# FerroAudioAmp.net
KiCad netlist of a schematic drawn in Altium Designer
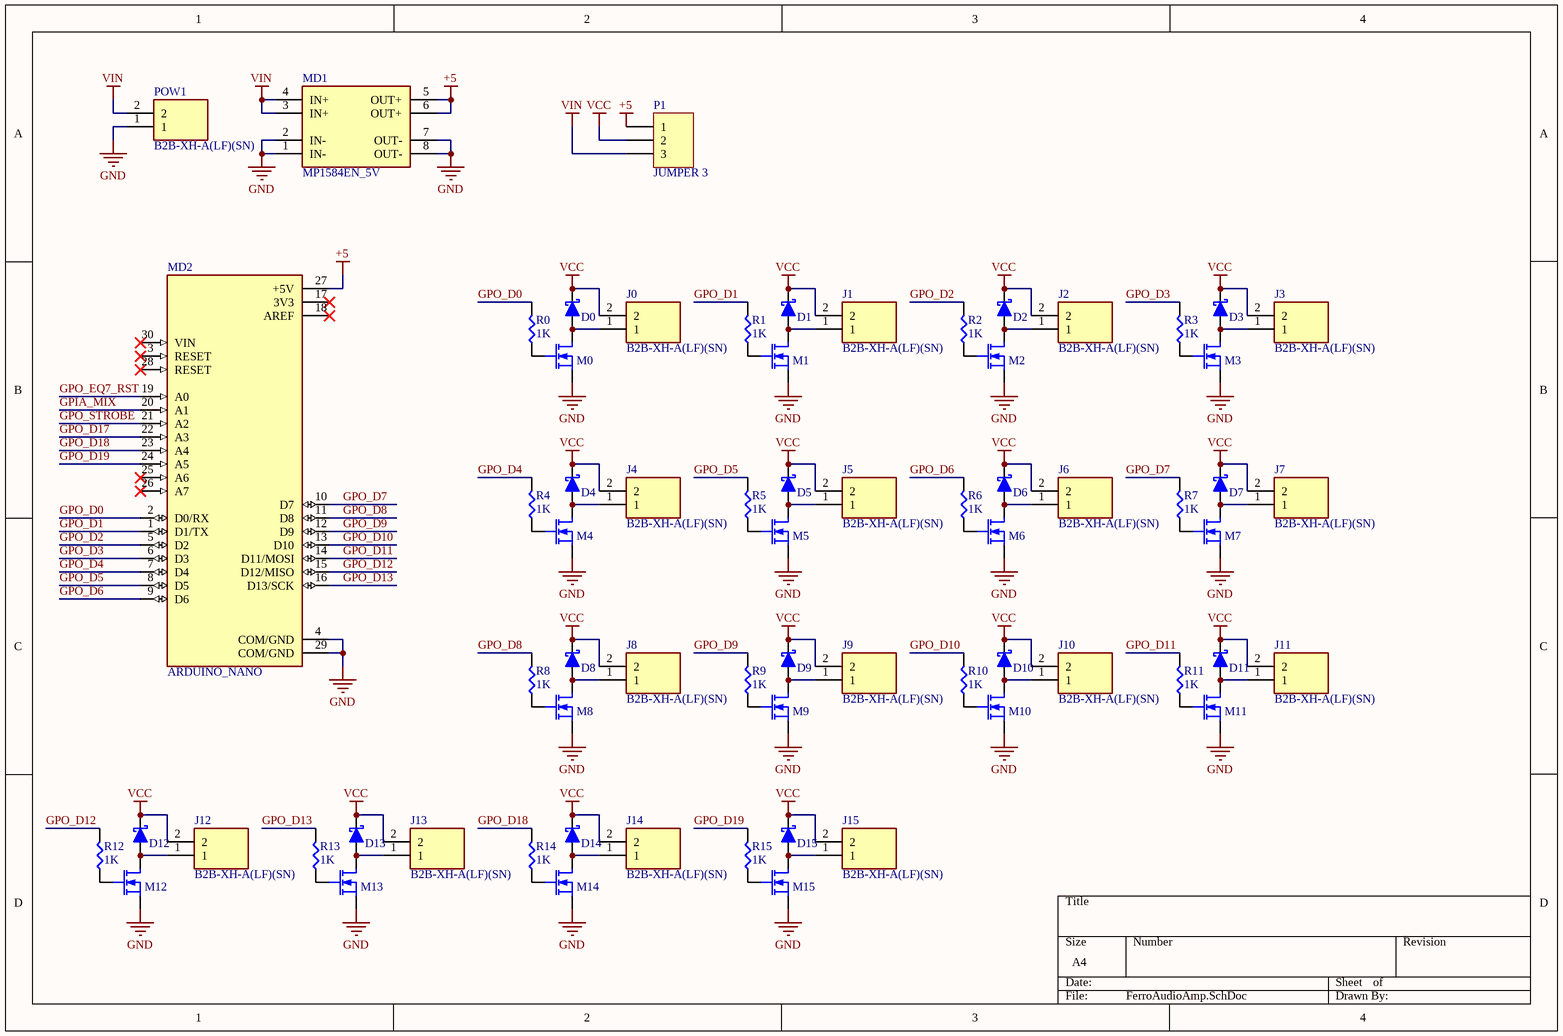
[diagram p0: FerroAudioAmp.SchDoc]

(export (version "E")
  (design (tool "Eeschema 10.0.6"))
  (components
    (comp (ref "D0")
      (value "RB521S30T1G")
      (footprint "SOD523")
      (description "Diode Schottky 30V 200mA (DC) Surface Mount SOD-523")
      (libsource (lib "FerroAudioAmp") (part "Diode Schottky"))
    )
    (comp (ref "D1")
      (value "RB521S30T1G")
      (footprint "SOD523")
      (description "Diode Schottky 30V 200mA (DC) Surface Mount SOD-523")
      (libsource (lib "FerroAudioAmp") (part "Diode Schottky"))
    )
    (comp (ref "D2")
      (value "RB521S30T1G")
      (footprint "SOD523")
      (description "Diode Schottky 30V 200mA (DC) Surface Mount SOD-523")
      (libsource (lib "FerroAudioAmp") (part "Diode Schottky"))
    )
    (comp (ref "D3")
      (value "RB521S30T1G")
      (footprint "SOD523")
      (description "Diode Schottky 30V 200mA (DC) Surface Mount SOD-523")
      (libsource (lib "FerroAudioAmp") (part "Diode Schottky"))
    )
    (comp (ref "D4")
      (value "RB521S30T1G")
      (footprint "SOD523")
      (description "Diode Schottky 30V 200mA (DC) Surface Mount SOD-523")
      (libsource (lib "FerroAudioAmp") (part "Diode Schottky"))
    )
    (comp (ref "D5")
      (value "RB521S30T1G")
      (footprint "SOD523")
      (description "Diode Schottky 30V 200mA (DC) Surface Mount SOD-523")
      (libsource (lib "FerroAudioAmp") (part "Diode Schottky"))
    )
    (comp (ref "D6")
      (value "RB521S30T1G")
      (footprint "SOD523")
      (description "Diode Schottky 30V 200mA (DC) Surface Mount SOD-523")
      (libsource (lib "FerroAudioAmp") (part "Diode Schottky"))
    )
    (comp (ref "D7")
      (value "RB521S30T1G")
      (footprint "SOD523")
      (description "Diode Schottky 30V 200mA (DC) Surface Mount SOD-523")
      (libsource (lib "FerroAudioAmp") (part "Diode Schottky"))
    )
    (comp (ref "D8")
      (value "RB521S30T1G")
      (footprint "SOD523")
      (description "Diode Schottky 30V 200mA (DC) Surface Mount SOD-523")
      (libsource (lib "FerroAudioAmp") (part "Diode Schottky"))
    )
    (comp (ref "D9")
      (value "RB521S30T1G")
      (footprint "SOD523")
      (description "Diode Schottky 30V 200mA (DC) Surface Mount SOD-523")
      (libsource (lib "FerroAudioAmp") (part "Diode Schottky"))
    )
    (comp (ref "D10")
      (value "RB521S30T1G")
      (footprint "SOD523")
      (description "Diode Schottky 30V 200mA (DC) Surface Mount SOD-523")
      (libsource (lib "FerroAudioAmp") (part "Diode Schottky"))
    )
    (comp (ref "D11")
      (value "RB521S30T1G")
      (footprint "SOD523")
      (description "Diode Schottky 30V 200mA (DC) Surface Mount SOD-523")
      (libsource (lib "FerroAudioAmp") (part "Diode Schottky"))
    )
    (comp (ref "D12")
      (value "RB521S30T1G")
      (footprint "SOD523")
      (description "Diode Schottky 30V 200mA (DC) Surface Mount SOD-523")
      (libsource (lib "FerroAudioAmp") (part "Diode Schottky"))
    )
    (comp (ref "D13")
      (value "RB521S30T1G")
      (footprint "SOD523")
      (description "Diode Schottky 30V 200mA (DC) Surface Mount SOD-523")
      (libsource (lib "FerroAudioAmp") (part "Diode Schottky"))
    )
    (comp (ref "D14")
      (value "RB521S30T1G")
      (footprint "SOD523")
      (description "Diode Schottky 30V 200mA (DC) Surface Mount SOD-523")
      (libsource (lib "FerroAudioAmp") (part "Diode Schottky"))
    )
    (comp (ref "D15")
      (value "RB521S30T1G")
      (footprint "SOD523")
      (description "Diode Schottky 30V 200mA (DC) Surface Mount SOD-523")
      (libsource (lib "FerroAudioAmp") (part "Diode Schottky"))
    )
    (comp (ref "J0")
      (value "B2B-XH-A(LF)(SN)")
      (footprint "JST_B2B-XH-A(LF)(SN)")
      (description "Connector Header Through Hole 2 position 0.098 (2.50mm)")
      (fields (field (name "MF") "JST Sales"))
      (libsource (lib "FerroAudioAmp") (part "B2B-XH-A(LF)(SN)"))
    )
    (comp (ref "J1")
      (value "B2B-XH-A(LF)(SN)")
      (footprint "JST_B2B-XH-A(LF)(SN)")
      (description "Connector Header Through Hole 2 position 0.098 (2.50mm)")
      (fields (field (name "MF") "JST Sales"))
      (libsource (lib "FerroAudioAmp") (part "B2B-XH-A(LF)(SN)"))
    )
    (comp (ref "J2")
      (value "B2B-XH-A(LF)(SN)")
      (footprint "JST_B2B-XH-A(LF)(SN)")
      (description "Connector Header Through Hole 2 position 0.098 (2.50mm)")
      (fields (field (name "MF") "JST Sales"))
      (libsource (lib "FerroAudioAmp") (part "B2B-XH-A(LF)(SN)"))
    )
    (comp (ref "J3")
      (value "B2B-XH-A(LF)(SN)")
      (footprint "JST_B2B-XH-A(LF)(SN)")
      (description "Connector Header Through Hole 2 position 0.098 (2.50mm)")
      (fields (field (name "MF") "JST Sales"))
      (libsource (lib "FerroAudioAmp") (part "B2B-XH-A(LF)(SN)"))
    )
    (comp (ref "J4")
      (value "B2B-XH-A(LF)(SN)")
      (footprint "JST_B2B-XH-A(LF)(SN)")
      (description "Connector Header Through Hole 2 position 0.098 (2.50mm)")
      (fields (field (name "MF") "JST Sales"))
      (libsource (lib "FerroAudioAmp") (part "B2B-XH-A(LF)(SN)"))
    )
    (comp (ref "J5")
      (value "B2B-XH-A(LF)(SN)")
      (footprint "JST_B2B-XH-A(LF)(SN)")
      (description "Connector Header Through Hole 2 position 0.098 (2.50mm)")
      (fields (field (name "MF") "JST Sales"))
      (libsource (lib "FerroAudioAmp") (part "B2B-XH-A(LF)(SN)"))
    )
    (comp (ref "J6")
      (value "B2B-XH-A(LF)(SN)")
      (footprint "JST_B2B-XH-A(LF)(SN)")
      (description "Connector Header Through Hole 2 position 0.098 (2.50mm)")
      (fields (field (name "MF") "JST Sales"))
      (libsource (lib "FerroAudioAmp") (part "B2B-XH-A(LF)(SN)"))
    )
    (comp (ref "J7")
      (value "B2B-XH-A(LF)(SN)")
      (footprint "JST_B2B-XH-A(LF)(SN)")
      (description "Connector Header Through Hole 2 position 0.098 (2.50mm)")
      (fields (field (name "MF") "JST Sales"))
      (libsource (lib "FerroAudioAmp") (part "B2B-XH-A(LF)(SN)"))
    )
    (comp (ref "J8")
      (value "B2B-XH-A(LF)(SN)")
      (footprint "JST_B2B-XH-A(LF)(SN)")
      (description "Connector Header Through Hole 2 position 0.098 (2.50mm)")
      (fields (field (name "MF") "JST Sales"))
      (libsource (lib "FerroAudioAmp") (part "B2B-XH-A(LF)(SN)"))
    )
    (comp (ref "J9")
      (value "B2B-XH-A(LF)(SN)")
      (footprint "JST_B2B-XH-A(LF)(SN)")
      (description "Connector Header Through Hole 2 position 0.098 (2.50mm)")
      (fields (field (name "MF") "JST Sales"))
      (libsource (lib "FerroAudioAmp") (part "B2B-XH-A(LF)(SN)"))
    )
    (comp (ref "J10")
      (value "B2B-XH-A(LF)(SN)")
      (footprint "JST_B2B-XH-A(LF)(SN)")
      (description "Connector Header Through Hole 2 position 0.098 (2.50mm)")
      (fields (field (name "MF") "JST Sales"))
      (libsource (lib "FerroAudioAmp") (part "B2B-XH-A(LF)(SN)"))
    )
    (comp (ref "J11")
      (value "B2B-XH-A(LF)(SN)")
      (footprint "JST_B2B-XH-A(LF)(SN)")
      (description "Connector Header Through Hole 2 position 0.098 (2.50mm)")
      (fields (field (name "MF") "JST Sales"))
      (libsource (lib "FerroAudioAmp") (part "B2B-XH-A(LF)(SN)"))
    )
    (comp (ref "J12")
      (value "B2B-XH-A(LF)(SN)")
      (footprint "JST_B2B-XH-A(LF)(SN)")
      (description "Connector Header Through Hole 2 position 0.098 (2.50mm)")
      (fields (field (name "MF") "JST Sales"))
      (libsource (lib "FerroAudioAmp") (part "B2B-XH-A(LF)(SN)"))
    )
    (comp (ref "J13")
      (value "B2B-XH-A(LF)(SN)")
      (footprint "JST_B2B-XH-A(LF)(SN)")
      (description "Connector Header Through Hole 2 position 0.098 (2.50mm)")
      (fields (field (name "MF") "JST Sales"))
      (libsource (lib "FerroAudioAmp") (part "B2B-XH-A(LF)(SN)"))
    )
    (comp (ref "J14")
      (value "B2B-XH-A(LF)(SN)")
      (footprint "JST_B2B-XH-A(LF)(SN)")
      (description "Connector Header Through Hole 2 position 0.098 (2.50mm)")
      (fields (field (name "MF") "JST Sales"))
      (libsource (lib "FerroAudioAmp") (part "B2B-XH-A(LF)(SN)"))
    )
    (comp (ref "J15")
      (value "B2B-XH-A(LF)(SN)")
      (footprint "JST_B2B-XH-A(LF)(SN)")
      (description "Connector Header Through Hole 2 position 0.098 (2.50mm)")
      (fields (field (name "MF") "JST Sales"))
      (libsource (lib "FerroAudioAmp") (part "B2B-XH-A(LF)(SN)"))
    )
    (comp (ref "M0")
      (value "DMN2056U-7")
      (footprint "SOT23_L")
      (description "N-Channel 20V 4A (Ta) 940mW Surface Mount SOT-23-3")
      (libsource (lib "altium-import") (part "root_0_MOSFET-N_"))
    )
    (comp (ref "M1")
      (value "DMN2056U-7")
      (footprint "SOT23_L")
      (description "N-Channel 20V 4A (Ta) 940mW Surface Mount SOT-23-3")
      (libsource (lib "altium-import") (part "root_0_MOSFET-N_"))
    )
    (comp (ref "M2")
      (value "DMN2056U-7")
      (footprint "SOT23_L")
      (description "N-Channel 20V 4A (Ta) 940mW Surface Mount SOT-23-3")
      (libsource (lib "altium-import") (part "root_0_MOSFET-N_"))
    )
    (comp (ref "M3")
      (value "DMN2056U-7")
      (footprint "SOT23_L")
      (description "N-Channel 20V 4A (Ta) 940mW Surface Mount SOT-23-3")
      (libsource (lib "altium-import") (part "root_0_MOSFET-N_"))
    )
    (comp (ref "M4")
      (value "DMN2056U-7")
      (footprint "SOT23_L")
      (description "N-Channel 20V 4A (Ta) 940mW Surface Mount SOT-23-3")
      (libsource (lib "altium-import") (part "root_0_MOSFET-N_"))
    )
    (comp (ref "M5")
      (value "DMN2056U-7")
      (footprint "SOT23_L")
      (description "N-Channel 20V 4A (Ta) 940mW Surface Mount SOT-23-3")
      (libsource (lib "altium-import") (part "root_0_MOSFET-N_"))
    )
    (comp (ref "M6")
      (value "DMN2056U-7")
      (footprint "SOT23_L")
      (description "N-Channel 20V 4A (Ta) 940mW Surface Mount SOT-23-3")
      (libsource (lib "altium-import") (part "root_0_MOSFET-N_"))
    )
    (comp (ref "M7")
      (value "DMN2056U-7")
      (footprint "SOT23_L")
      (description "N-Channel 20V 4A (Ta) 940mW Surface Mount SOT-23-3")
      (libsource (lib "altium-import") (part "root_0_MOSFET-N_"))
    )
    (comp (ref "M8")
      (value "DMN2056U-7")
      (footprint "SOT23_L")
      (description "N-Channel 20V 4A (Ta) 940mW Surface Mount SOT-23-3")
      (libsource (lib "altium-import") (part "root_0_MOSFET-N_"))
    )
    (comp (ref "M9")
      (value "DMN2056U-7")
      (footprint "SOT23_L")
      (description "N-Channel 20V 4A (Ta) 940mW Surface Mount SOT-23-3")
      (libsource (lib "altium-import") (part "root_0_MOSFET-N_"))
    )
    (comp (ref "M10")
      (value "DMN2056U-7")
      (footprint "SOT23_L")
      (description "N-Channel 20V 4A (Ta) 940mW Surface Mount SOT-23-3")
      (libsource (lib "altium-import") (part "root_0_MOSFET-N_"))
    )
    (comp (ref "M11")
      (value "DMN2056U-7")
      (footprint "SOT23_L")
      (description "N-Channel 20V 4A (Ta) 940mW Surface Mount SOT-23-3")
      (libsource (lib "altium-import") (part "root_0_MOSFET-N_"))
    )
    (comp (ref "M12")
      (value "DMN2056U-7")
      (footprint "SOT23_L")
      (description "N-Channel 20V 4A (Ta) 940mW Surface Mount SOT-23-3")
      (libsource (lib "altium-import") (part "root_0_MOSFET-N_"))
    )
    (comp (ref "M13")
      (value "DMN2056U-7")
      (footprint "SOT23_L")
      (description "N-Channel 20V 4A (Ta) 940mW Surface Mount SOT-23-3")
      (libsource (lib "altium-import") (part "root_0_MOSFET-N_"))
    )
    (comp (ref "M14")
      (value "DMN2056U-7")
      (footprint "SOT23_L")
      (description "N-Channel 20V 4A (Ta) 940mW Surface Mount SOT-23-3")
      (libsource (lib "altium-import") (part "root_0_MOSFET-N_"))
    )
    (comp (ref "M15")
      (value "DMN2056U-7")
      (footprint "SOT23_L")
      (description "N-Channel 20V 4A (Ta) 940mW Surface Mount SOT-23-3")
      (libsource (lib "altium-import") (part "root_0_MOSFET-N_"))
    )
    (comp (ref "MD1")
      (value "MP1584EN_5V")
      (footprint "MP1584EN_5V")
      (description "DC-DC 6.5-28V in 5V out module")
      (libsource (lib "FerroAudioAmp") (part "MP1584EN_5V"))
    )
    (comp (ref "MD2")
      (value "ARDUINO_NANO")
      (footprint "SHIELD_ARDUINO_NANO")
      (description "ATSAMD21G18A Arduino Nano 33 IoT SAM D ARMÂ® CortexÂ®-M0+ MCU 32-Bit Embedded Evaluation Board")
      (fields (field (name "MP") "ARDUINO NANO") (field (name "MF") "Arduino"))
      (libsource (lib "altium-import") (part "root_0_ARDUINO_NANO_"))
    )
    (comp (ref "P1")
      (value "JUMPER 3")
      (footprint "HDR1X3")
      (description "Header, 3-Pin")
      (fields (field (name "PUBLISHER") "Altium Limited"))
      (libsource (lib "Miscellaneous Connectors") (part "Header 3"))
    )
    (comp (ref "POW1")
      (value "B2B-XH-A(LF)(SN)")
      (footprint "JST_B2B-XH-A(LF)(SN)")
      (description "Connector Header Through Hole 2 position 0.098 (2.50mm)")
      (fields (field (name "MF") "JST Sales"))
      (libsource (lib "FerroAudioAmp") (part "B2B-XH-A(LF)(SN)"))
    )
    (comp (ref "R0") (value "1K") (footprint "0603") (libsource (lib "altium-import") (part "root_1_Res_")))
    (comp (ref "R1") (value "1K") (footprint "0603") (libsource (lib "altium-import") (part "root_1_Res_")))
    (comp (ref "R2") (value "1K") (footprint "0603") (libsource (lib "altium-import") (part "root_1_Res_")))
    (comp (ref "R3") (value "1K") (footprint "0603") (libsource (lib "altium-import") (part "root_1_Res_")))
    (comp (ref "R4") (value "1K") (footprint "0603") (libsource (lib "altium-import") (part "root_1_Res_")))
    (comp (ref "R5") (value "1K") (footprint "0603") (libsource (lib "altium-import") (part "root_1_Res_")))
    (comp (ref "R6") (value "1K") (footprint "0603") (libsource (lib "altium-import") (part "root_1_Res_")))
    (comp (ref "R7") (value "1K") (footprint "0603") (libsource (lib "altium-import") (part "root_1_Res_")))
    (comp (ref "R8") (value "1K") (footprint "0603") (libsource (lib "altium-import") (part "root_1_Res_")))
    (comp (ref "R9") (value "1K") (footprint "0603") (libsource (lib "altium-import") (part "root_1_Res_")))
    (comp (ref "R10") (value "1K") (footprint "0603") (libsource (lib "altium-import") (part "root_1_Res_")))
    (comp (ref "R11") (value "1K") (footprint "0603") (libsource (lib "altium-import") (part "root_1_Res_")))
    (comp (ref "R12") (value "1K") (footprint "0603") (libsource (lib "altium-import") (part "root_1_Res_")))
    (comp (ref "R13") (value "1K") (footprint "0603") (libsource (lib "altium-import") (part "root_1_Res_")))
    (comp (ref "R14") (value "1K") (footprint "0603") (libsource (lib "altium-import") (part "root_1_Res_")))
    (comp (ref "R15") (value "1K") (footprint "0603") (libsource (lib "altium-import") (part "root_1_Res_")))
  )
  (nets
    (net (code "1") (name "+5") (class "Default")
      (node (ref "MD1") (pin "5") (pinfunction "OUT+_5") (pintype "passive"))
      (node (ref "MD1") (pin "6") (pinfunction "OUT+_6") (pintype "passive"))
      (node (ref "MD2") (pin "27") (pinfunction "+5V_27") (pintype "power_in"))
      (node (ref "P1") (pin "1") (pinfunction "1_1") (pintype "passive"))
    )
    (net (code "2") (name "/GPIA_MIX") (class "Default")
      (node (ref "MD2") (pin "20") (pinfunction "A1_20") (pintype "input"))
    )
    (net (code "3") (name "/GPO_D0") (class "Default")
      (node (ref "MD2") (pin "2") (pinfunction "D0/RX_2") (pintype "bidirectional"))
      (node (ref "R0") (pin "2") (pinfunction "2_2") (pintype "passive"))
    )
    (net (code "4") (name "/GPO_D1") (class "Default")
      (node (ref "MD2") (pin "1") (pinfunction "D1/TX_1") (pintype "bidirectional"))
      (node (ref "R1") (pin "2") (pinfunction "2_2") (pintype "passive"))
    )
    (net (code "5") (name "/GPO_D2") (class "Default")
      (node (ref "MD2") (pin "5") (pinfunction "D2_5") (pintype "bidirectional"))
      (node (ref "R2") (pin "2") (pinfunction "2_2") (pintype "passive"))
    )
    (net (code "6") (name "/GPO_D3") (class "Default")
      (node (ref "MD2") (pin "6") (pinfunction "D3_6") (pintype "bidirectional"))
      (node (ref "R3") (pin "2") (pinfunction "2_2") (pintype "passive"))
    )
    (net (code "7") (name "/GPO_D4") (class "Default")
      (node (ref "MD2") (pin "7") (pinfunction "D4_7") (pintype "bidirectional"))
      (node (ref "R4") (pin "2") (pinfunction "2_2") (pintype "passive"))
    )
    (net (code "8") (name "/GPO_D5") (class "Default")
      (node (ref "MD2") (pin "8") (pinfunction "D5_8") (pintype "bidirectional"))
      (node (ref "R5") (pin "2") (pinfunction "2_2") (pintype "passive"))
    )
    (net (code "9") (name "/GPO_D6") (class "Default")
      (node (ref "MD2") (pin "9") (pinfunction "D6_9") (pintype "bidirectional"))
      (node (ref "R6") (pin "2") (pinfunction "2_2") (pintype "passive"))
    )
    (net (code "10") (name "/GPO_D7") (class "Default")
      (node (ref "MD2") (pin "10") (pinfunction "D7_10") (pintype "bidirectional"))
      (node (ref "R7") (pin "2") (pinfunction "2_2") (pintype "passive"))
    )
    (net (code "11") (name "/GPO_D8") (class "Default")
      (node (ref "MD2") (pin "11") (pinfunction "D8_11") (pintype "bidirectional"))
      (node (ref "R8") (pin "2") (pinfunction "2_2") (pintype "passive"))
    )
    (net (code "12") (name "/GPO_D9") (class "Default")
      (node (ref "MD2") (pin "12") (pinfunction "D9_12") (pintype "bidirectional"))
      (node (ref "R9") (pin "2") (pinfunction "2_2") (pintype "passive"))
    )
    (net (code "13") (name "/GPO_D10") (class "Default")
      (node (ref "MD2") (pin "13") (pinfunction "D10_13") (pintype "bidirectional"))
      (node (ref "R10") (pin "2") (pinfunction "2_2") (pintype "passive"))
    )
    (net (code "14") (name "/GPO_D11") (class "Default")
      (node (ref "MD2") (pin "14") (pinfunction "D11/MOSI_14") (pintype "bidirectional"))
      (node (ref "R11") (pin "2") (pinfunction "2_2") (pintype "passive"))
    )
    (net (code "15") (name "/GPO_D12") (class "Default")
      (node (ref "MD2") (pin "15") (pinfunction "D12/MISO_15") (pintype "bidirectional"))
      (node (ref "R12") (pin "2") (pinfunction "2_2") (pintype "passive"))
    )
    (net (code "16") (name "/GPO_D13") (class "Default")
      (node (ref "MD2") (pin "16") (pinfunction "D13/SCK_16") (pintype "bidirectional"))
      (node (ref "R13") (pin "2") (pinfunction "2_2") (pintype "passive"))
    )
    (net (code "17") (name "/GPO_D17") (class "Default")
      (node (ref "MD2") (pin "22") (pinfunction "A3_22") (pintype "input"))
    )
    (net (code "18") (name "/GPO_D18") (class "Default")
      (node (ref "MD2") (pin "23") (pinfunction "A4_23") (pintype "input"))
      (node (ref "R14") (pin "2") (pinfunction "2_2") (pintype "passive"))
    )
    (net (code "19") (name "/GPO_D19") (class "Default")
      (node (ref "MD2") (pin "24") (pinfunction "A5_24") (pintype "input"))
      (node (ref "R15") (pin "2") (pinfunction "2_2") (pintype "passive"))
    )
    (net (code "20") (name "/GPO_EQ7_RST") (class "Default")
      (node (ref "MD2") (pin "19") (pinfunction "A0_19") (pintype "input"))
    )
    (net (code "21") (name "/GPO_STROBE") (class "Default")
      (node (ref "MD2") (pin "21") (pinfunction "A2_21") (pintype "input"))
    )
    (net (code "22") (name "GND") (class "Default")
      (node (ref "M0") (pin "2") (pinfunction "S_2") (pintype "passive"))
      (node (ref "M1") (pin "2") (pinfunction "S_2") (pintype "passive"))
      (node (ref "M10") (pin "2") (pinfunction "S_2") (pintype "passive"))
      (node (ref "M11") (pin "2") (pinfunction "S_2") (pintype "passive"))
      (node (ref "M12") (pin "2") (pinfunction "S_2") (pintype "passive"))
      (node (ref "M13") (pin "2") (pinfunction "S_2") (pintype "passive"))
      (node (ref "M14") (pin "2") (pinfunction "S_2") (pintype "passive"))
      (node (ref "M15") (pin "2") (pinfunction "S_2") (pintype "passive"))
      (node (ref "M2") (pin "2") (pinfunction "S_2") (pintype "passive"))
      (node (ref "M3") (pin "2") (pinfunction "S_2") (pintype "passive"))
      (node (ref "M4") (pin "2") (pinfunction "S_2") (pintype "passive"))
      (node (ref "M5") (pin "2") (pinfunction "S_2") (pintype "passive"))
      (node (ref "M6") (pin "2") (pinfunction "S_2") (pintype "passive"))
      (node (ref "M7") (pin "2") (pinfunction "S_2") (pintype "passive"))
      (node (ref "M8") (pin "2") (pinfunction "S_2") (pintype "passive"))
      (node (ref "M9") (pin "2") (pinfunction "S_2") (pintype "passive"))
      (node (ref "MD1") (pin "1") (pinfunction "IN-_1") (pintype "passive"))
      (node (ref "MD1") (pin "2") (pinfunction "IN-_2") (pintype "passive"))
      (node (ref "MD1") (pin "7") (pinfunction "OUT-_7") (pintype "passive"))
      (node (ref "MD1") (pin "8") (pinfunction "OUT-_8") (pintype "passive"))
      (node (ref "MD2") (pin "29") (pinfunction "COM/GND_29") (pintype "power_in"))
      (node (ref "MD2") (pin "4") (pinfunction "COM/GND_4") (pintype "power_in"))
      (node (ref "POW1") (pin "1") (pinfunction "1_1") (pintype "passive"))
    )
    (net (code "23") (name "Net-(M0-D)") (class "Default")
      (node (ref "D0") (pin "A") (pinfunction "A_A") (pintype "passive"))
      (node (ref "J0") (pin "1") (pinfunction "1_1") (pintype "passive"))
      (node (ref "M0") (pin "1") (pinfunction "D_1") (pintype "passive"))
    )
    (net (code "24") (name "Net-(M0-G)") (class "Default")
      (node (ref "M0") (pin "3") (pinfunction "G_3") (pintype "passive"))
      (node (ref "R0") (pin "1") (pinfunction "1_1") (pintype "passive"))
    )
    (net (code "25") (name "Net-(M1-D)") (class "Default")
      (node (ref "D1") (pin "A") (pinfunction "A_A") (pintype "passive"))
      (node (ref "J1") (pin "1") (pinfunction "1_1") (pintype "passive"))
      (node (ref "M1") (pin "1") (pinfunction "D_1") (pintype "passive"))
    )
    (net (code "26") (name "Net-(M1-G)") (class "Default")
      (node (ref "M1") (pin "3") (pinfunction "G_3") (pintype "passive"))
      (node (ref "R1") (pin "1") (pinfunction "1_1") (pintype "passive"))
    )
    (net (code "27") (name "Net-(M2-D)") (class "Default")
      (node (ref "D2") (pin "A") (pinfunction "A_A") (pintype "passive"))
      (node (ref "J2") (pin "1") (pinfunction "1_1") (pintype "passive"))
      (node (ref "M2") (pin "1") (pinfunction "D_1") (pintype "passive"))
    )
    (net (code "28") (name "Net-(M2-G)") (class "Default")
      (node (ref "M2") (pin "3") (pinfunction "G_3") (pintype "passive"))
      (node (ref "R2") (pin "1") (pinfunction "1_1") (pintype "passive"))
    )
    (net (code "29") (name "Net-(M3-D)") (class "Default")
      (node (ref "D3") (pin "A") (pinfunction "A_A") (pintype "passive"))
      (node (ref "J3") (pin "1") (pinfunction "1_1") (pintype "passive"))
      (node (ref "M3") (pin "1") (pinfunction "D_1") (pintype "passive"))
    )
    (net (code "30") (name "Net-(M3-G)") (class "Default")
      (node (ref "M3") (pin "3") (pinfunction "G_3") (pintype "passive"))
      (node (ref "R3") (pin "1") (pinfunction "1_1") (pintype "passive"))
    )
    (net (code "31") (name "Net-(M4-D)") (class "Default")
      (node (ref "D4") (pin "A") (pinfunction "A_A") (pintype "passive"))
      (node (ref "J4") (pin "1") (pinfunction "1_1") (pintype "passive"))
      (node (ref "M4") (pin "1") (pinfunction "D_1") (pintype "passive"))
    )
    (net (code "32") (name "Net-(M4-G)") (class "Default")
      (node (ref "M4") (pin "3") (pinfunction "G_3") (pintype "passive"))
      (node (ref "R4") (pin "1") (pinfunction "1_1") (pintype "passive"))
    )
    (net (code "33") (name "Net-(M5-D)") (class "Default")
      (node (ref "D5") (pin "A") (pinfunction "A_A") (pintype "passive"))
      (node (ref "J5") (pin "1") (pinfunction "1_1") (pintype "passive"))
      (node (ref "M5") (pin "1") (pinfunction "D_1") (pintype "passive"))
    )
    (net (code "34") (name "Net-(M5-G)") (class "Default")
      (node (ref "M5") (pin "3") (pinfunction "G_3") (pintype "passive"))
      (node (ref "R5") (pin "1") (pinfunction "1_1") (pintype "passive"))
    )
    (net (code "35") (name "Net-(M6-D)") (class "Default")
      (node (ref "D6") (pin "A") (pinfunction "A_A") (pintype "passive"))
      (node (ref "J6") (pin "1") (pinfunction "1_1") (pintype "passive"))
      (node (ref "M6") (pin "1") (pinfunction "D_1") (pintype "passive"))
    )
    (net (code "36") (name "Net-(M6-G)") (class "Default")
      (node (ref "M6") (pin "3") (pinfunction "G_3") (pintype "passive"))
      (node (ref "R6") (pin "1") (pinfunction "1_1") (pintype "passive"))
    )
    (net (code "37") (name "Net-(M7-D)") (class "Default")
      (node (ref "D7") (pin "A") (pinfunction "A_A") (pintype "passive"))
      (node (ref "J7") (pin "1") (pinfunction "1_1") (pintype "passive"))
      (node (ref "M7") (pin "1") (pinfunction "D_1") (pintype "passive"))
    )
    (net (code "38") (name "Net-(M7-G)") (class "Default")
      (node (ref "M7") (pin "3") (pinfunction "G_3") (pintype "passive"))
      (node (ref "R7") (pin "1") (pinfunction "1_1") (pintype "passive"))
    )
    (net (code "39") (name "Net-(M8-D)") (class "Default")
      (node (ref "D8") (pin "A") (pinfunction "A_A") (pintype "passive"))
      (node (ref "J8") (pin "1") (pinfunction "1_1") (pintype "passive"))
      (node (ref "M8") (pin "1") (pinfunction "D_1") (pintype "passive"))
    )
    (net (code "40") (name "Net-(M8-G)") (class "Default")
      (node (ref "M8") (pin "3") (pinfunction "G_3") (pintype "passive"))
      (node (ref "R8") (pin "1") (pinfunction "1_1") (pintype "passive"))
    )
    (net (code "41") (name "Net-(M9-D)") (class "Default")
      (node (ref "D9") (pin "A") (pinfunction "A_A") (pintype "passive"))
      (node (ref "J9") (pin "1") (pinfunction "1_1") (pintype "passive"))
      (node (ref "M9") (pin "1") (pinfunction "D_1") (pintype "passive"))
    )
    (net (code "42") (name "Net-(M9-G)") (class "Default")
      (node (ref "M9") (pin "3") (pinfunction "G_3") (pintype "passive"))
      (node (ref "R9") (pin "1") (pinfunction "1_1") (pintype "passive"))
    )
    (net (code "43") (name "Net-(M10-D)") (class "Default")
      (node (ref "D10") (pin "A") (pinfunction "A_A") (pintype "passive"))
      (node (ref "J10") (pin "1") (pinfunction "1_1") (pintype "passive"))
      (node (ref "M10") (pin "1") (pinfunction "D_1") (pintype "passive"))
    )
    (net (code "44") (name "Net-(M10-G)") (class "Default")
      (node (ref "M10") (pin "3") (pinfunction "G_3") (pintype "passive"))
      (node (ref "R10") (pin "1") (pinfunction "1_1") (pintype "passive"))
    )
    (net (code "45") (name "Net-(M11-D)") (class "Default")
      (node (ref "D11") (pin "A") (pinfunction "A_A") (pintype "passive"))
      (node (ref "J11") (pin "1") (pinfunction "1_1") (pintype "passive"))
      (node (ref "M11") (pin "1") (pinfunction "D_1") (pintype "passive"))
    )
    (net (code "46") (name "Net-(M11-G)") (class "Default")
      (node (ref "M11") (pin "3") (pinfunction "G_3") (pintype "passive"))
      (node (ref "R11") (pin "1") (pinfunction "1_1") (pintype "passive"))
    )
    (net (code "47") (name "Net-(M12-D)") (class "Default")
      (node (ref "D12") (pin "A") (pinfunction "A_A") (pintype "passive"))
      (node (ref "J12") (pin "1") (pinfunction "1_1") (pintype "passive"))
      (node (ref "M12") (pin "1") (pinfunction "D_1") (pintype "passive"))
    )
    (net (code "48") (name "Net-(M12-G)") (class "Default")
      (node (ref "M12") (pin "3") (pinfunction "G_3") (pintype "passive"))
      (node (ref "R12") (pin "1") (pinfunction "1_1") (pintype "passive"))
    )
    (net (code "49") (name "Net-(M13-D)") (class "Default")
      (node (ref "D13") (pin "A") (pinfunction "A_A") (pintype "passive"))
      (node (ref "J13") (pin "1") (pinfunction "1_1") (pintype "passive"))
      (node (ref "M13") (pin "1") (pinfunction "D_1") (pintype "passive"))
    )
    (net (code "50") (name "Net-(M13-G)") (class "Default")
      (node (ref "M13") (pin "3") (pinfunction "G_3") (pintype "passive"))
      (node (ref "R13") (pin "1") (pinfunction "1_1") (pintype "passive"))
    )
    (net (code "51") (name "Net-(M14-D)") (class "Default")
      (node (ref "D14") (pin "A") (pinfunction "A_A") (pintype "passive"))
      (node (ref "J14") (pin "1") (pinfunction "1_1") (pintype "passive"))
      (node (ref "M14") (pin "1") (pinfunction "D_1") (pintype "passive"))
    )
    (net (code "52") (name "Net-(M14-G)") (class "Default")
      (node (ref "M14") (pin "3") (pinfunction "G_3") (pintype "passive"))
      (node (ref "R14") (pin "1") (pinfunction "1_1") (pintype "passive"))
    )
    (net (code "53") (name "Net-(M15-D)") (class "Default")
      (node (ref "D15") (pin "A") (pinfunction "A_A") (pintype "passive"))
      (node (ref "J15") (pin "1") (pinfunction "1_1") (pintype "passive"))
      (node (ref "M15") (pin "1") (pinfunction "D_1") (pintype "passive"))
    )
    (net (code "54") (name "Net-(M15-G)") (class "Default")
      (node (ref "M15") (pin "3") (pinfunction "G_3") (pintype "passive"))
      (node (ref "R15") (pin "1") (pinfunction "1_1") (pintype "passive"))
    )
    (net (code "55") (name "VCC") (class "Default")
      (node (ref "D0") (pin "C") (pinfunction "C_C") (pintype "passive"))
      (node (ref "D1") (pin "C") (pinfunction "C_C") (pintype "passive"))
      (node (ref "D10") (pin "C") (pinfunction "C_C") (pintype "passive"))
      (node (ref "D11") (pin "C") (pinfunction "C_C") (pintype "passive"))
      (node (ref "D12") (pin "C") (pinfunction "C_C") (pintype "passive"))
      (node (ref "D13") (pin "C") (pinfunction "C_C") (pintype "passive"))
      (node (ref "D14") (pin "C") (pinfunction "C_C") (pintype "passive"))
      (node (ref "D15") (pin "C") (pinfunction "C_C") (pintype "passive"))
      (node (ref "D2") (pin "C") (pinfunction "C_C") (pintype "passive"))
      (node (ref "D3") (pin "C") (pinfunction "C_C") (pintype "passive"))
      (node (ref "D4") (pin "C") (pinfunction "C_C") (pintype "passive"))
      (node (ref "D5") (pin "C") (pinfunction "C_C") (pintype "passive"))
      (node (ref "D6") (pin "C") (pinfunction "C_C") (pintype "passive"))
      (node (ref "D7") (pin "C") (pinfunction "C_C") (pintype "passive"))
      (node (ref "D8") (pin "C") (pinfunction "C_C") (pintype "passive"))
      (node (ref "D9") (pin "C") (pinfunction "C_C") (pintype "passive"))
      (node (ref "J0") (pin "2") (pinfunction "2_2") (pintype "passive"))
      (node (ref "J1") (pin "2") (pinfunction "2_2") (pintype "passive"))
      (node (ref "J10") (pin "2") (pinfunction "2_2") (pintype "passive"))
      (node (ref "J11") (pin "2") (pinfunction "2_2") (pintype "passive"))
      (node (ref "J12") (pin "2") (pinfunction "2_2") (pintype "passive"))
      (node (ref "J13") (pin "2") (pinfunction "2_2") (pintype "passive"))
      (node (ref "J14") (pin "2") (pinfunction "2_2") (pintype "passive"))
      (node (ref "J15") (pin "2") (pinfunction "2_2") (pintype "passive"))
      (node (ref "J2") (pin "2") (pinfunction "2_2") (pintype "passive"))
      (node (ref "J3") (pin "2") (pinfunction "2_2") (pintype "passive"))
      (node (ref "J4") (pin "2") (pinfunction "2_2") (pintype "passive"))
      (node (ref "J5") (pin "2") (pinfunction "2_2") (pintype "passive"))
      (node (ref "J6") (pin "2") (pinfunction "2_2") (pintype "passive"))
      (node (ref "J7") (pin "2") (pinfunction "2_2") (pintype "passive"))
      (node (ref "J8") (pin "2") (pinfunction "2_2") (pintype "passive"))
      (node (ref "J9") (pin "2") (pinfunction "2_2") (pintype "passive"))
      (node (ref "P1") (pin "2") (pinfunction "2_2") (pintype "passive"))
    )
    (net (code "56") (name "VIN") (class "Default")
      (node (ref "MD1") (pin "3") (pinfunction "IN+_3") (pintype "passive"))
      (node (ref "MD1") (pin "4") (pinfunction "IN+_4") (pintype "passive"))
      (node (ref "P1") (pin "3") (pinfunction "3_3") (pintype "passive"))
      (node (ref "POW1") (pin "2") (pinfunction "2_2") (pintype "passive"))
    )
    (net (code "57") (name "unconnected-(MD2-3V3-Pad17)") (class "Default")
      (node (ref "MD2") (pin "17") (pinfunction "3V3_17") (pintype "power_in+no_connect"))
    )
    (net (code "58") (name "unconnected-(MD2-A6-Pad25)") (class "Default")
      (node (ref "MD2") (pin "25") (pinfunction "A6_25") (pintype "input+no_connect"))
    )
    (net (code "59") (name "unconnected-(MD2-A7-Pad26)") (class "Default")
      (node (ref "MD2") (pin "26") (pinfunction "A7_26") (pintype "input+no_connect"))
    )
    (net (code "60") (name "unconnected-(MD2-AREF-Pad18)") (class "Default")
      (node (ref "MD2") (pin "18") (pinfunction "AREF_18") (pintype "power_in+no_connect"))
    )
    (net (code "61") (name "unconnected-(MD2-RESET-Pad3)") (class "Default")
      (node (ref "MD2") (pin "3") (pinfunction "RESET_3") (pintype "input+no_connect"))
    )
    (net (code "62") (name "unconnected-(MD2-RESET-Pad28)") (class "Default")
      (node (ref "MD2") (pin "28") (pinfunction "RESET_28") (pintype "input+no_connect"))
    )
    (net (code "63") (name "unconnected-(MD2-VIN-Pad30)") (class "Default")
      (node (ref "MD2") (pin "30") (pinfunction "VIN_30") (pintype "input+no_connect"))
    )
  )
)
